# rtc.net
KiCad netlist of a schematic drawn in Altium Designer
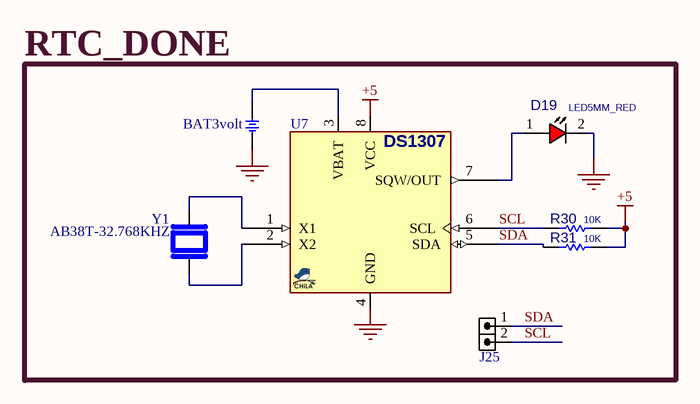
[diagram p0: rtc.SchDoc]

(export (version "E")
  (design (tool "Eeschema 10.0.6"))
  (components
    (comp (ref "BT1")
      (value "BAT3volt")
      (footprint "BTH2032")
      (description "BATTERY HOLDER, CR2032")
      (libsource (lib "battery") (part "BATH_CR2032"))
    )
    (comp (ref "D19")
      (value "LED5MM_RED")
      (footprint "LED5MM_RED")
      (description "LED, THD, 5MM, RED")
      (fields (field (name "MANF") "MANF") (field (name "MANF_P#") "MANF_PART#"))
      (libsource (lib "led(diode)") (part "LED_THD_5MM_RED"))
    )
    (comp (ref "J25")
      (value "HDRM2")
      (footprint "HDR_M_1X2")
      (description "CONN, HEADER, Male, pitch: 2.54mm, 2POS")
      (libsource (lib "conn_header_2.54mm_st") (part "HDR_M_1X2"))
    )
    (comp (ref "R30")
      (value "10K")
      (footprint "R025W_AX04")
      (description "RESISTOR, THD")
      (fields (field (name "MANF_P#") "RK73H1ETTP4701F") (field (name "MANF") "KOA SPEER"))
      (libsource (lib "passive_thd") (part "RES_THD"))
    )
    (comp (ref "R31")
      (value "10K")
      (footprint "R025W_AX04")
      (description "RESISTOR, THD")
      (fields (field (name "MANF_P#") "RK73H1ETTP4701F") (field (name "MANF") "KOA SPEER"))
      (libsource (lib "passive_thd") (part "RES_THD"))
    )
    (comp (ref "U7")
      (value "DS1307")
      (footprint "DIP_8")
      (description "Real-Time Clock, 64 X8, I2C, 56B, Batt")
      (fields (field (name "MANF") "Maxim Integrated") (field (name "MANF_P#") "DS1307N+"))
      (libsource (lib "rtc") (part "DS1307_DIP8"))
    )
    (comp (ref "Y1")
      (value "AB38T-32.768KHZ")
      (footprint "XTAL_AB38T-32.768KHZ")
      (libsource (lib "AB38T-32.768KHZ") (part "AB38T-32.768KHZ"))
    )
  )
  (nets
    (net (code "1") (name "+5") (class "Default")
      (node (ref "R30") (pin "1") (pinfunction "1_1") (pintype "passive"))
      (node (ref "R31") (pin "1") (pinfunction "1_1") (pintype "passive"))
      (node (ref "U7") (pin "8") (pinfunction "VCC_8") (pintype "power_in"))
    )
    (net (code "2") (name "/SCL") (class "Default")
      (node (ref "J25") (pin "2") (pinfunction "2_2") (pintype "passive"))
      (node (ref "R30") (pin "2") (pinfunction "2_2") (pintype "passive"))
      (node (ref "U7") (pin "6") (pinfunction "SCL_6") (pintype "input"))
    )
    (net (code "3") (name "/SDA") (class "Default")
      (node (ref "J25") (pin "1") (pinfunction "1_1") (pintype "passive"))
      (node (ref "R31") (pin "2") (pinfunction "2_2") (pintype "passive"))
      (node (ref "U7") (pin "5") (pinfunction "SDA_5") (pintype "bidirectional"))
    )
    (net (code "4") (name "GND") (class "Default")
      (node (ref "BT1") (pin "2") (pinfunction "2_2") (pintype "passive"))
      (node (ref "D19") (pin "2") (pinfunction "CATHODE_2") (pintype "passive"))
      (node (ref "U7") (pin "4") (pinfunction "GND_4") (pintype "power_in"))
    )
    (net (code "5") (name "Net-(D19-ANODE)") (class "Default")
      (node (ref "D19") (pin "1") (pinfunction "ANODE_1") (pintype "passive"))
      (node (ref "U7") (pin "7") (pinfunction "SQW/OUT_7") (pintype "output"))
    )
    (net (code "6") (name "Net-(U7-VBAT)") (class "Default")
      (node (ref "BT1") (pin "1") (pinfunction "1_1") (pintype "passive"))
      (node (ref "U7") (pin "3") (pinfunction "VBAT_3") (pintype "power_in"))
    )
    (net (code "7") (name "Net-(U7-X1)") (class "Default")
      (node (ref "U7") (pin "1") (pinfunction "X1_1") (pintype "input"))
      (node (ref "Y1") (pin "2") (pinfunction "2_2") (pintype "passive"))
    )
    (net (code "8") (name "Net-(U7-X2)") (class "Default")
      (node (ref "U7") (pin "2") (pinfunction "X2_2") (pintype "input"))
      (node (ref "Y1") (pin "1") (pinfunction "1_1") (pintype "passive"))
    )
  )
)
